# ESP8266.net
KiCad netlist of a schematic drawn in Altium Designer
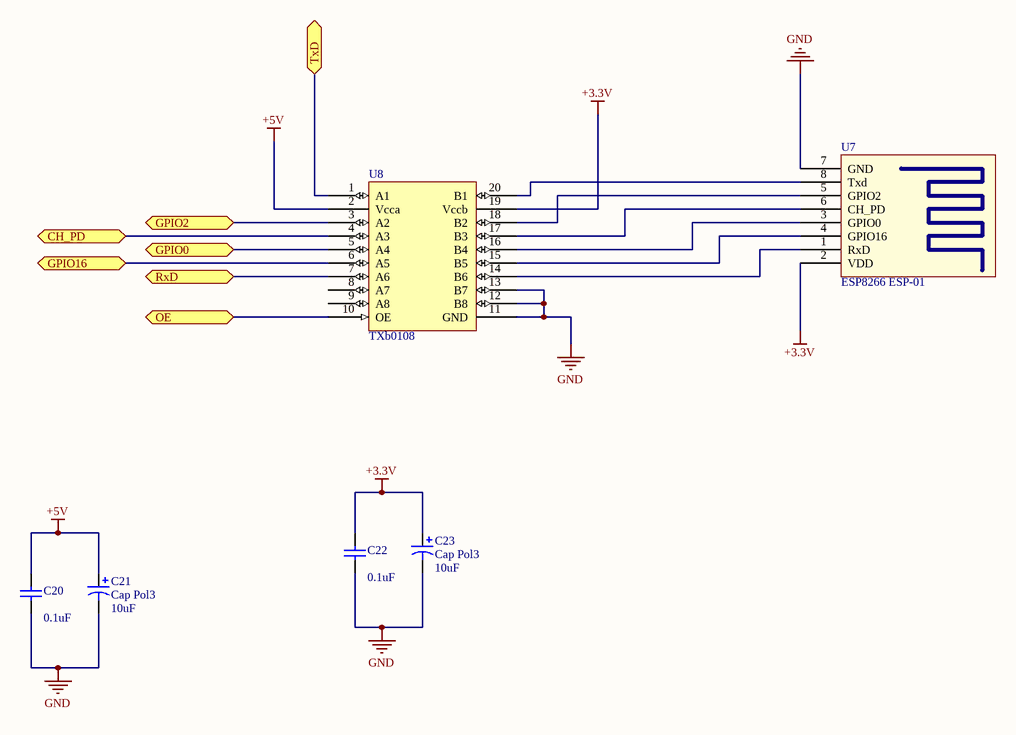
[diagram p0: ESP8266.SchDoc]

(export (version "E")
  (design (tool "Eeschema 10.0.6"))
  (components
    (comp (ref "C20")
      (value "0.1uF")
      (footprint "C1206")
      (description "Capacitor (Semiconductor SIM Model)")
      (fields (field (name "Comment") "Cap Semi") (field (name "PUBLISHER") "Altium Limited"))
      (libsource (lib "Miscellaneous Devices") (part "Cap Semi"))
    )
    (comp (ref "C21")
      (value "Cap Pol3")
      (footprint "C0805")
      (description "Polarized Capacitor (Surface Mount)")
      (fields (field (name "ALTIUM_VALUE") "10uF") (field (name "PUBLISHER") "Altium Limited"))
      (libsource (lib "Miscellaneous Devices") (part "Cap Pol3"))
    )
    (comp (ref "C22")
      (value "0.1uF")
      (footprint "C1206")
      (description "Capacitor (Semiconductor SIM Model)")
      (fields (field (name "Comment") "Cap Semi") (field (name "PUBLISHER") "Altium Limited"))
      (libsource (lib "Miscellaneous Devices") (part "Cap Semi"))
    )
    (comp (ref "C23")
      (value "Cap Pol3")
      (footprint "C0805")
      (description "Polarized Capacitor (Surface Mount)")
      (fields (field (name "ALTIUM_VALUE") "10uF") (field (name "PUBLISHER") "Altium Limited"))
      (libsource (lib "Miscellaneous Devices") (part "Cap Pol3"))
    )
    (comp (ref "U7")
      (value "ESP8266 ESP-01")
      (footprint "ESP8266:ESP8266 ESP-01")
      (libsource (lib "ESP8266") (part "ESP8266 ESP-01"))
    )
    (comp (ref "U8") (value "TXb0108") (footprint "TXB0108") (libsource (lib "TXB0108") (part "TXb0108")))
  )
  (nets
    (net (code "1") (name "+3.3V") (class "Default")
      (node (ref "C22") (pin "1") (pinfunction "1_1") (pintype "passive"))
      (node (ref "C23") (pin "1") (pinfunction "1_1") (pintype "passive"))
      (node (ref "U7") (pin "2") (pinfunction "VDD_2") (pintype "passive"))
      (node (ref "U8") (pin "19") (pinfunction "Vccb_19") (pintype "power_in"))
    )
    (net (code "2") (name "+5V") (class "Default")
      (node (ref "C20") (pin "1") (pinfunction "1_1") (pintype "passive"))
      (node (ref "C21") (pin "1") (pinfunction "1_1") (pintype "passive"))
      (node (ref "U8") (pin "2") (pinfunction "Vcca_2") (pintype "power_in"))
    )
    (net (code "3") (name "/CH_PD") (class "Default")
      (node (ref "U8") (pin "4") (pinfunction "A3_4") (pintype "bidirectional"))
    )
    (net (code "4") (name "/GPIO0") (class "Default")
      (node (ref "U8") (pin "5") (pinfunction "A4_5") (pintype "bidirectional"))
    )
    (net (code "5") (name "/GPIO2") (class "Default")
      (node (ref "U8") (pin "3") (pinfunction "A2_3") (pintype "bidirectional"))
    )
    (net (code "6") (name "/GPIO16") (class "Default")
      (node (ref "U8") (pin "6") (pinfunction "A5_6") (pintype "bidirectional"))
    )
    (net (code "7") (name "/OE") (class "Default")
      (node (ref "U8") (pin "10") (pinfunction "OE_10") (pintype "input"))
    )
    (net (code "8") (name "/RxD") (class "Default")
      (node (ref "U8") (pin "7") (pinfunction "A6_7") (pintype "bidirectional"))
    )
    (net (code "9") (name "/TxD") (class "Default")
      (node (ref "U8") (pin "1") (pinfunction "A1_1") (pintype "bidirectional"))
    )
    (net (code "10") (name "GND") (class "Default")
      (node (ref "C20") (pin "2") (pinfunction "2_2") (pintype "passive"))
      (node (ref "C21") (pin "2") (pinfunction "2_2") (pintype "passive"))
      (node (ref "C22") (pin "2") (pinfunction "2_2") (pintype "passive"))
      (node (ref "C23") (pin "2") (pinfunction "2_2") (pintype "passive"))
      (node (ref "U7") (pin "7") (pinfunction "GND_7") (pintype "passive"))
      (node (ref "U8") (pin "11") (pinfunction "GND_11") (pintype "power_in"))
      (node (ref "U8") (pin "12") (pinfunction "B8_12") (pintype "bidirectional"))
      (node (ref "U8") (pin "13") (pinfunction "B7_13") (pintype "bidirectional"))
    )
    (net (code "11") (name "Net-(U7-CH_PD)") (class "Default")
      (node (ref "U7") (pin "6") (pinfunction "CH_PD_6") (pintype "passive"))
      (node (ref "U8") (pin "17") (pinfunction "B3_17") (pintype "bidirectional"))
    )
    (net (code "12") (name "Net-(U7-GPIO0)") (class "Default")
      (node (ref "U7") (pin "3") (pinfunction "GPIO0_3") (pintype "passive"))
      (node (ref "U8") (pin "16") (pinfunction "B4_16") (pintype "bidirectional"))
    )
    (net (code "13") (name "Net-(U7-GPIO2)") (class "Default")
      (node (ref "U7") (pin "5") (pinfunction "GPIO2_5") (pintype "passive"))
      (node (ref "U8") (pin "18") (pinfunction "B2_18") (pintype "bidirectional"))
    )
    (net (code "14") (name "Net-(U7-GPIO16)") (class "Default")
      (node (ref "U7") (pin "4") (pinfunction "GPIO16_4") (pintype "passive"))
      (node (ref "U8") (pin "15") (pinfunction "B5_15") (pintype "bidirectional"))
    )
    (net (code "15") (name "Net-(U7-RxD)") (class "Default")
      (node (ref "U7") (pin "1") (pinfunction "RxD_1") (pintype "passive"))
      (node (ref "U8") (pin "14") (pinfunction "B6_14") (pintype "bidirectional"))
    )
    (net (code "16") (name "Net-(U7-Txd)") (class "Default")
      (node (ref "U7") (pin "8") (pinfunction "Txd_8") (pintype "passive"))
      (node (ref "U8") (pin "20") (pinfunction "B1_20") (pintype "bidirectional"))
    )
    (net (code "17") (name "unconnected-(U8-A7-Pad8)") (class "Default")
      (node (ref "U8") (pin "8") (pinfunction "A7_8") (pintype "bidirectional"))
    )
    (net (code "18") (name "unconnected-(U8-A8-Pad9)") (class "Default")
      (node (ref "U8") (pin "9") (pinfunction "A8_9") (pintype "bidirectional"))
    )
  )
)
